# pendant_board2.net
KiCad netlist of a schematic drawn in EAGLE
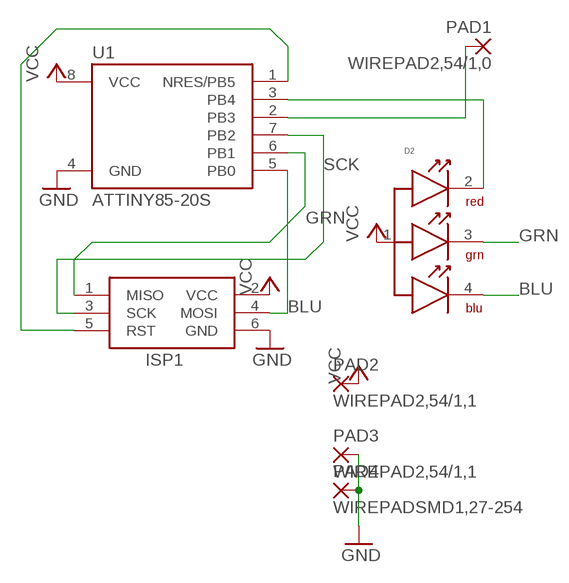
[diagram p0: schematic, sheet 1]

(export (version "E")
  (design (tool "Eeschema 10.0.6"))
  (components
    (comp (ref "D2")
      (value "SM1210RGB")
      (footprint "eagle-import:SM1210RGB")
      (libsource (lib "eagle-import") (part "SM1210RGB"))
    )
    (comp (ref "ISP1")
      (value "AVRISP-BOX")
      (footprint "eagle-import:AVRISP-BOX")
      (libsource (lib "eagle-import") (part "AVRISP-BOX"))
    )
    (comp (ref "PAD1")
      (value "WIREPAD2,54/1,0")
      (footprint "eagle-import:2,54_1,0")
      (libsource (lib "eagle-import") (part "WIREPAD2,54/1,0"))
    )
    (comp (ref "PAD2")
      (value "WIREPAD2,54/1,1")
      (footprint "eagle-import:2,54_1,1")
      (libsource (lib "eagle-import") (part "WIREPAD2,54/1,1"))
    )
    (comp (ref "PAD3")
      (value "WIREPAD2,54/1,1")
      (footprint "eagle-import:2,54_1,1")
      (libsource (lib "eagle-import") (part "WIREPAD2,54/1,1"))
    )
    (comp (ref "PAD4")
      (value "WIREPADSMD1,27-254")
      (footprint "eagle-import:SMD1,27-2,54")
      (libsource (lib "eagle-import") (part "WIREPADSMD1,27-254"))
    )
    (comp (ref "U1")
      (value "ATTINY85-20S")
      (footprint "eagle-import:SOIC8_EIAJ_208MIL")
      (libsource (lib "eagle-import") (part "ATTINY85S-20"))
    )
  )
  (nets
    (net (code "1") (name "/BLU") (class "Default")
      (node (ref "D2") (pin "4") (pinfunction "BLU_4") (pintype "bidirectional"))
      (node (ref "ISP1") (pin "4") (pinfunction "MOSI_4") (pintype "output"))
      (node (ref "U1") (pin "5") (pinfunction "PB0_5") (pintype "bidirectional"))
    )
    (net (code "2") (name "/GRN") (class "Default")
      (node (ref "D2") (pin "3") (pinfunction "GRN_3") (pintype "bidirectional"))
      (node (ref "ISP1") (pin "1") (pinfunction "MISO_1") (pintype "input"))
      (node (ref "U1") (pin "6") (pinfunction "PB1_6") (pintype "bidirectional"))
    )
    (net (code "3") (name "/SCK") (class "Default")
      (node (ref "ISP1") (pin "3") (pinfunction "SCK_3") (pintype "output"))
      (node (ref "U1") (pin "7") (pinfunction "PB2_7") (pintype "bidirectional"))
    )
    (net (code "4") (name "GND") (class "Default")
      (node (ref "ISP1") (pin "6") (pinfunction "GND_6") (pintype "power_in"))
      (node (ref "PAD3") (pin "1") (pinfunction "P_1") (pintype "passive"))
      (node (ref "PAD4") (pin "1") (pinfunction "P_1") (pintype "passive"))
      (node (ref "U1") (pin "4") (pinfunction "GND_4") (pintype "power_in"))
    )
    (net (code "5") (name "Net-(D2-RED)") (class "Default")
      (node (ref "D2") (pin "2") (pinfunction "RED_2") (pintype "bidirectional"))
      (node (ref "U1") (pin "3") (pinfunction "PB4_3") (pintype "bidirectional"))
    )
    (net (code "6") (name "Net-(ISP1-RST)") (class "Default")
      (node (ref "ISP1") (pin "5") (pinfunction "RST_5") (pintype "output"))
      (node (ref "U1") (pin "1") (pinfunction "NRES/PB5_1") (pintype "bidirectional"))
    )
    (net (code "7") (name "Net-(PAD1-P)") (class "Default")
      (node (ref "PAD1") (pin "1") (pinfunction "P_1") (pintype "passive"))
      (node (ref "U1") (pin "2") (pinfunction "PB3_2") (pintype "bidirectional"))
    )
    (net (code "8") (name "VCC") (class "Default")
      (node (ref "D2") (pin "1") (pinfunction "VCC_1") (pintype "power_in"))
      (node (ref "ISP1") (pin "2") (pinfunction "VCC_2") (pintype "power_in"))
      (node (ref "PAD2") (pin "1") (pinfunction "P_1") (pintype "passive"))
      (node (ref "U1") (pin "8") (pinfunction "VCC_8") (pintype "power_in"))
    )
  )
)
